# maze_board.net
KiCad netlist of a schematic drawn in EAGLE
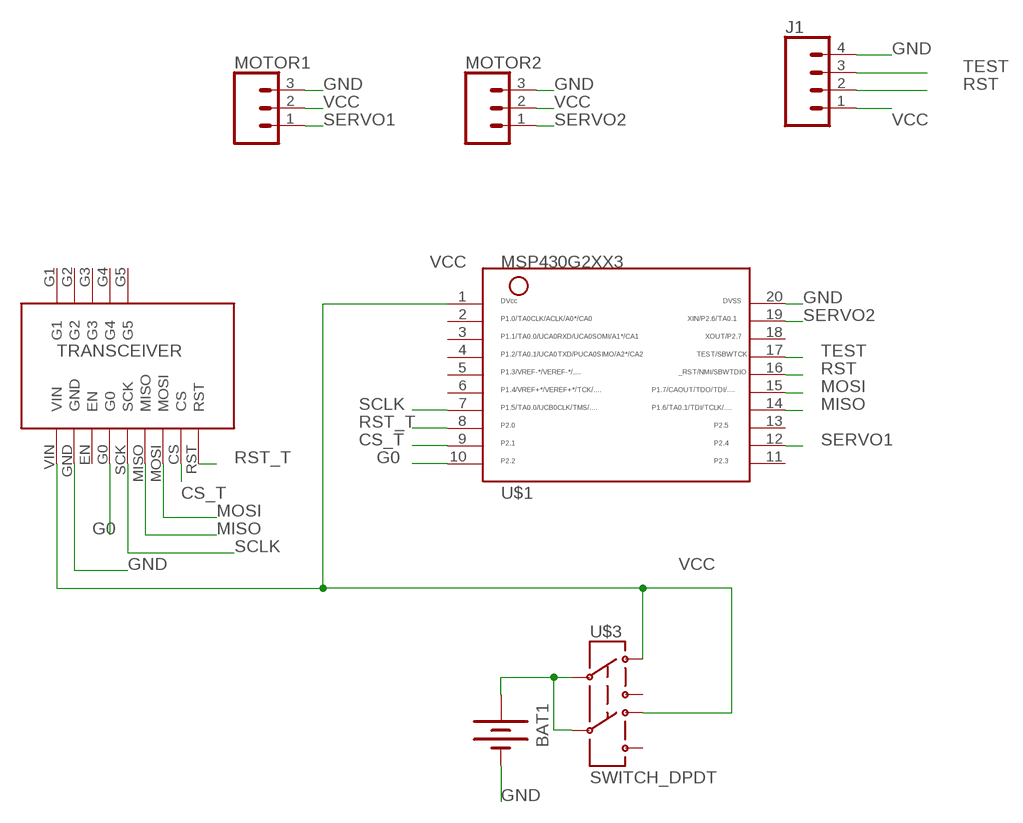
[diagram p0: schematic, sheet 1]

(export (version "E")
  (design (tool "Eeschema 10.0.6"))
  (components
    (comp (ref "BAT1")
      (value "BATTERY")
      (footprint "eagle-import:BATTERY_PACK_2AA")
      (libsource (lib "eagle-import") (part "BATTERY"))
    )
    (comp (ref "J1")
      (value "CONN_04LOCK")
      (footprint "eagle-import:1X04_LOCK")
      (libsource (lib "eagle-import") (part "CONN_04LOCK"))
    )
    (comp (ref "MOTOR1")
      (value "CONN_03LOCK")
      (footprint "eagle-import:1X03_LOCK")
      (libsource (lib "eagle-import") (part "CONN_03LOCK"))
    )
    (comp (ref "MOTOR2")
      (value "CONN_03LOCK")
      (footprint "eagle-import:1X03_LOCK")
      (libsource (lib "eagle-import") (part "CONN_03LOCK"))
    )
    (comp (ref "U$1")
      (value "MSP430G2XX3TSSOP")
      (footprint "eagle-import:PW20")
      (libsource (lib "eagle-import") (part "MSP430G2XX3TSSOP"))
    )
    (comp (ref "U$3")
      (value "SWITCH_DPDT")
      (footprint "eagle-import:JS_DPDT_TH")
      (libsource (lib "eagle-import") (part "SWITCH_DPDT"))
    )
    (comp (ref "U$4")
      (value "ADAFRUIT-RFM69HCW-TRANSCEIVER")
      (footprint "eagle-import:ADAFRUIT-RFM69HCW-TRANSCEIVER")
      (libsource (lib "eagle-import") (part "ADAFRUIT-RFM69HCW-TRANSCEIVER"))
    )
  )
  (nets
    (net (code "1") (name "/CS_T") (class "Default")
      (node (ref "U$1") (pin "9") (pinfunction "9_9") (pintype "bidirectional"))
      (node (ref "U$4") (pin "CS") (pinfunction "CS_CS") (pintype "bidirectional"))
    )
    (net (code "2") (name "/G0") (class "Default")
      (node (ref "U$1") (pin "10") (pinfunction "10_10") (pintype "bidirectional"))
      (node (ref "U$4") (pin "G0") (pinfunction "G0_G0") (pintype "bidirectional"))
    )
    (net (code "3") (name "/GND") (class "Default")
      (node (ref "BAT1") (pin "GND") (pinfunction "-_GND") (pintype "power_in"))
      (node (ref "J1") (pin "4") (pinfunction "4_4") (pintype "passive"))
      (node (ref "MOTOR1") (pin "3") (pinfunction "3_3") (pintype "passive"))
      (node (ref "MOTOR2") (pin "3") (pinfunction "3_3") (pintype "passive"))
      (node (ref "U$1") (pin "20") (pinfunction "20_20") (pintype "bidirectional"))
      (node (ref "U$4") (pin "GND") (pinfunction "GND_GND") (pintype "bidirectional"))
    )
    (net (code "4") (name "/MISO") (class "Default")
      (node (ref "U$1") (pin "14") (pinfunction "14_14") (pintype "bidirectional"))
      (node (ref "U$4") (pin "MISO") (pinfunction "MISO_MISO") (pintype "bidirectional"))
    )
    (net (code "5") (name "/MOSI") (class "Default")
      (node (ref "U$1") (pin "15") (pinfunction "15_15") (pintype "bidirectional"))
      (node (ref "U$4") (pin "MOSI") (pinfunction "MOSI_MOSI") (pintype "bidirectional"))
    )
    (net (code "6") (name "/RST") (class "Default")
      (node (ref "J1") (pin "2") (pinfunction "2_2") (pintype "passive"))
      (node (ref "U$1") (pin "16") (pinfunction "16_16") (pintype "bidirectional"))
    )
    (net (code "7") (name "/RST_T") (class "Default")
      (node (ref "U$1") (pin "8") (pinfunction "8_8") (pintype "bidirectional"))
      (node (ref "U$4") (pin "RST") (pinfunction "RST_RST") (pintype "bidirectional"))
    )
    (net (code "8") (name "/SCLK") (class "Default")
      (node (ref "U$1") (pin "7") (pinfunction "7_7") (pintype "bidirectional"))
      (node (ref "U$4") (pin "SCK") (pinfunction "SCK_SCK") (pintype "bidirectional"))
    )
    (net (code "9") (name "/SERVO1") (class "Default")
      (node (ref "MOTOR1") (pin "1") (pinfunction "1_1") (pintype "passive"))
      (node (ref "U$1") (pin "12") (pinfunction "12_12") (pintype "bidirectional"))
    )
    (net (code "10") (name "/SERVO2") (class "Default")
      (node (ref "MOTOR2") (pin "1") (pinfunction "1_1") (pintype "passive"))
      (node (ref "U$1") (pin "19") (pinfunction "19_19") (pintype "bidirectional"))
    )
    (net (code "11") (name "/TEST") (class "Default")
      (node (ref "J1") (pin "3") (pinfunction "3_3") (pintype "passive"))
      (node (ref "U$1") (pin "17") (pinfunction "17_17") (pintype "bidirectional"))
    )
    (net (code "12") (name "/VCC") (class "Default")
      (node (ref "J1") (pin "1") (pinfunction "1_1") (pintype "passive"))
      (node (ref "MOTOR1") (pin "2") (pinfunction "2_2") (pintype "passive"))
      (node (ref "MOTOR2") (pin "2") (pinfunction "2_2") (pintype "passive"))
      (node (ref "U$1") (pin "1") (pinfunction "1_1") (pintype "bidirectional"))
      (node (ref "U$3") (pin "1") (pinfunction "1_1") (pintype "bidirectional"))
      (node (ref "U$3") (pin "4") (pinfunction "4_4") (pintype "bidirectional"))
      (node (ref "U$4") (pin "VIN") (pinfunction "VIN_VIN") (pintype "bidirectional"))
    )
    (net (code "13") (name "Net-(BAT1-+)") (class "Default")
      (node (ref "BAT1") (pin "3V") (pinfunction "+_3V") (pintype "power_in"))
      (node (ref "U$3") (pin "2") (pinfunction "2_2") (pintype "bidirectional"))
      (node (ref "U$3") (pin "5") (pinfunction "5_5") (pintype "bidirectional"))
    )
    (net (code "14") (name "unconnected-(U$1-Pad2)") (class "Default")
      (node (ref "U$1") (pin "2") (pinfunction "2_2") (pintype "bidirectional"))
    )
    (net (code "15") (name "unconnected-(U$1-Pad3)") (class "Default")
      (node (ref "U$1") (pin "3") (pinfunction "3_3") (pintype "bidirectional"))
    )
    (net (code "16") (name "unconnected-(U$1-Pad4)") (class "Default")
      (node (ref "U$1") (pin "4") (pinfunction "4_4") (pintype "bidirectional"))
    )
    (net (code "17") (name "unconnected-(U$1-Pad5)") (class "Default")
      (node (ref "U$1") (pin "5") (pinfunction "5_5") (pintype "bidirectional"))
    )
    (net (code "18") (name "unconnected-(U$1-Pad6)") (class "Default")
      (node (ref "U$1") (pin "6") (pinfunction "6_6") (pintype "bidirectional"))
    )
    (net (code "19") (name "unconnected-(U$1-Pad11)") (class "Default")
      (node (ref "U$1") (pin "11") (pinfunction "11_11") (pintype "bidirectional"))
    )
    (net (code "20") (name "unconnected-(U$1-Pad13)") (class "Default")
      (node (ref "U$1") (pin "13") (pinfunction "13_13") (pintype "bidirectional"))
    )
    (net (code "21") (name "unconnected-(U$1-Pad18)") (class "Default")
      (node (ref "U$1") (pin "18") (pinfunction "18_18") (pintype "bidirectional"))
    )
    (net (code "22") (name "unconnected-(U$3-Pad3)") (class "Default")
      (node (ref "U$3") (pin "3") (pinfunction "3_3") (pintype "bidirectional"))
    )
    (net (code "23") (name "unconnected-(U$3-Pad6)") (class "Default")
      (node (ref "U$3") (pin "6") (pinfunction "6_6") (pintype "bidirectional"))
    )
    (net (code "24") (name "unconnected-(U$4-PadEN)") (class "Default")
      (node (ref "U$4") (pin "EN") (pinfunction "EN_EN") (pintype "bidirectional"))
    )
    (net (code "25") (name "unconnected-(U$4-PadG1)") (class "Default")
      (node (ref "U$4") (pin "G1") (pinfunction "G1_G1") (pintype "bidirectional"))
    )
    (net (code "26") (name "unconnected-(U$4-PadG2)") (class "Default")
      (node (ref "U$4") (pin "G2") (pinfunction "G2_G2") (pintype "bidirectional"))
    )
    (net (code "27") (name "unconnected-(U$4-PadG3)") (class "Default")
      (node (ref "U$4") (pin "G3") (pinfunction "G3_G3") (pintype "bidirectional"))
    )
    (net (code "28") (name "unconnected-(U$4-PadG4)") (class "Default")
      (node (ref "U$4") (pin "G4") (pinfunction "G4_G4") (pintype "bidirectional"))
    )
    (net (code "29") (name "unconnected-(U$4-PadG5)") (class "Default")
      (node (ref "U$4") (pin "G5") (pinfunction "G5_G5") (pintype "bidirectional"))
    )
  )
)
